# MSP-EXP430F5529LP.net
KiCad netlist of a schematic drawn in EAGLE
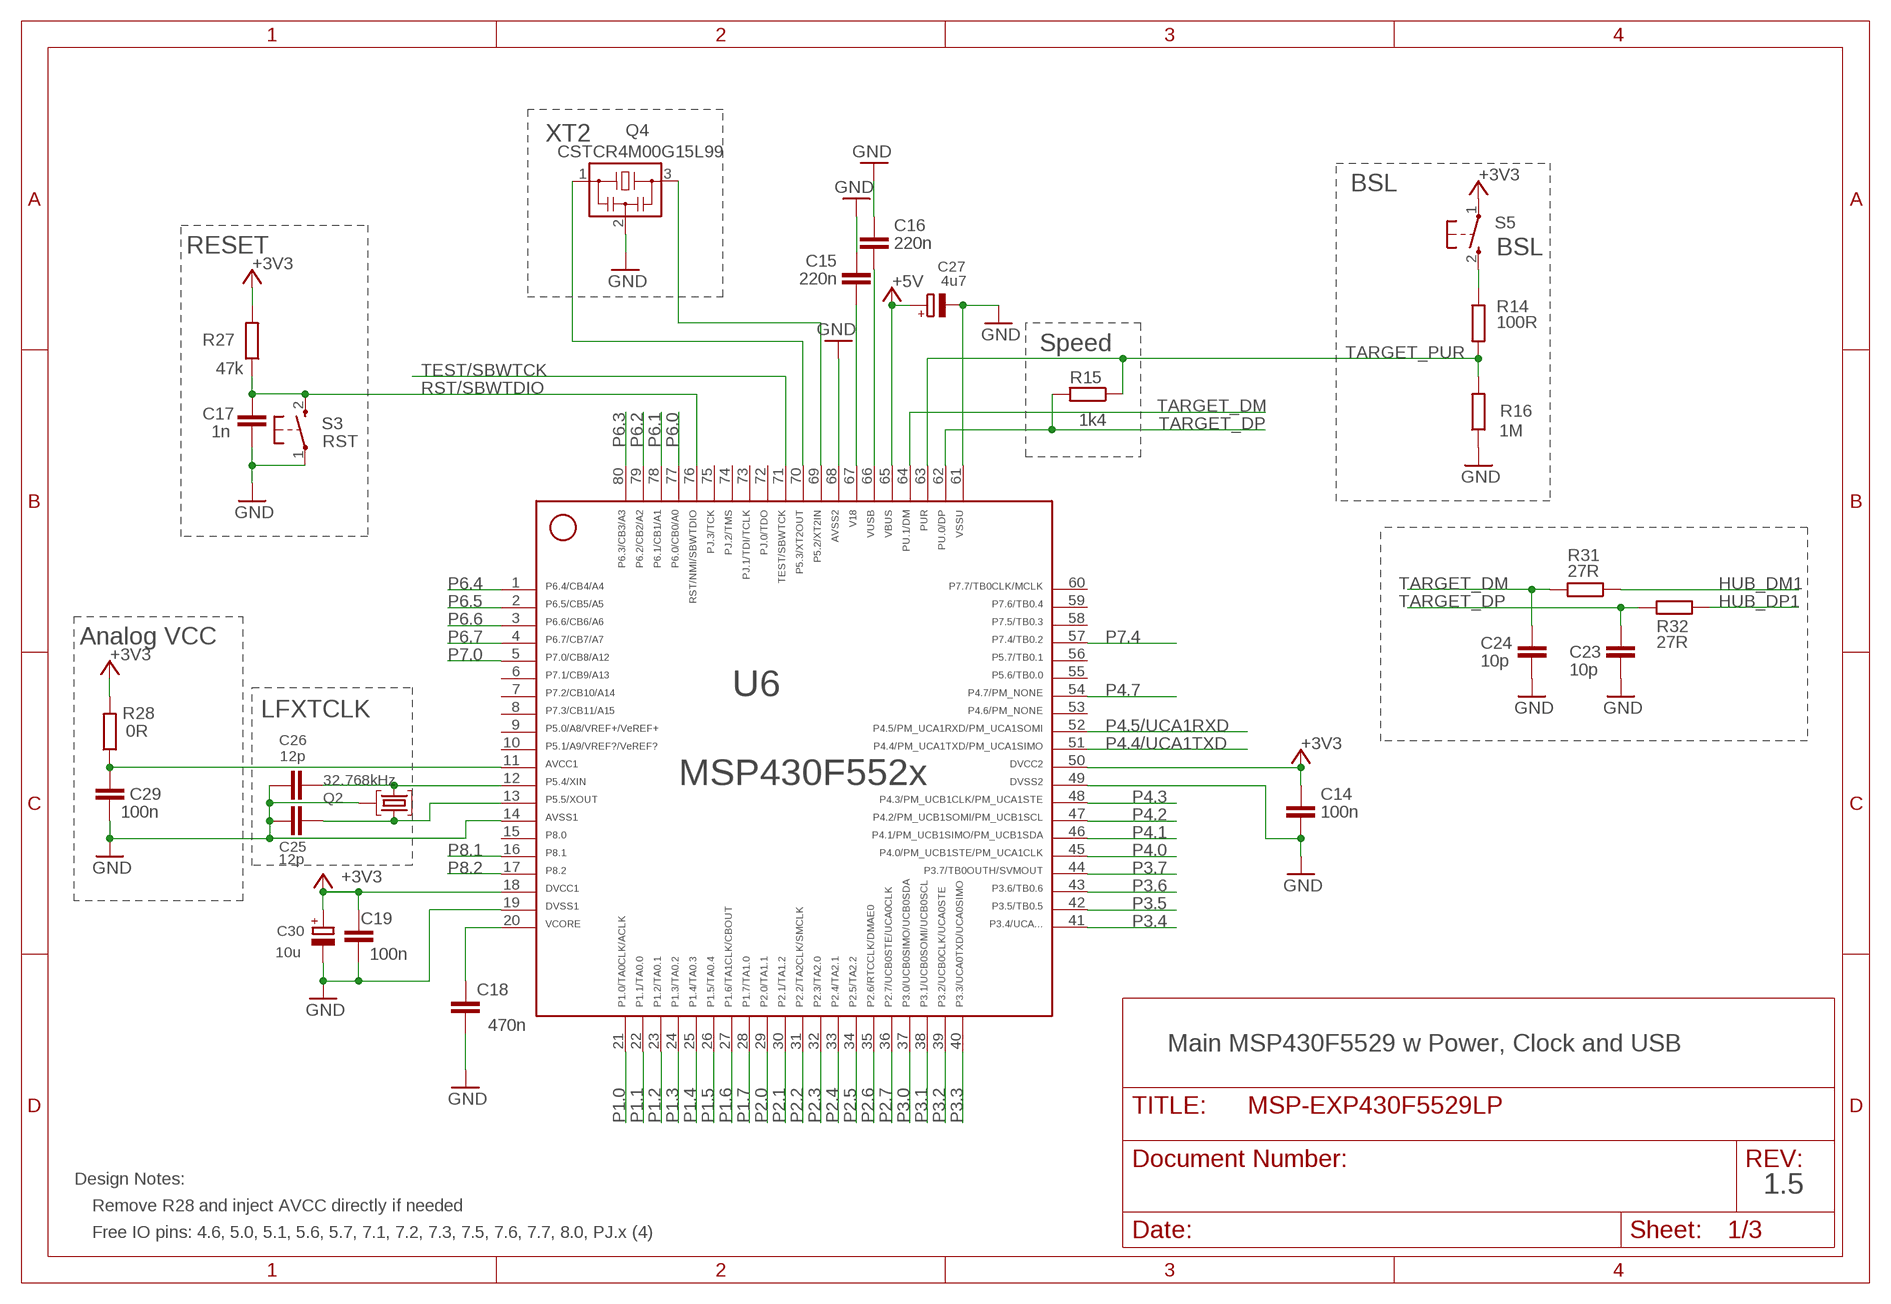
[diagram p0: schematic, sheet 1]
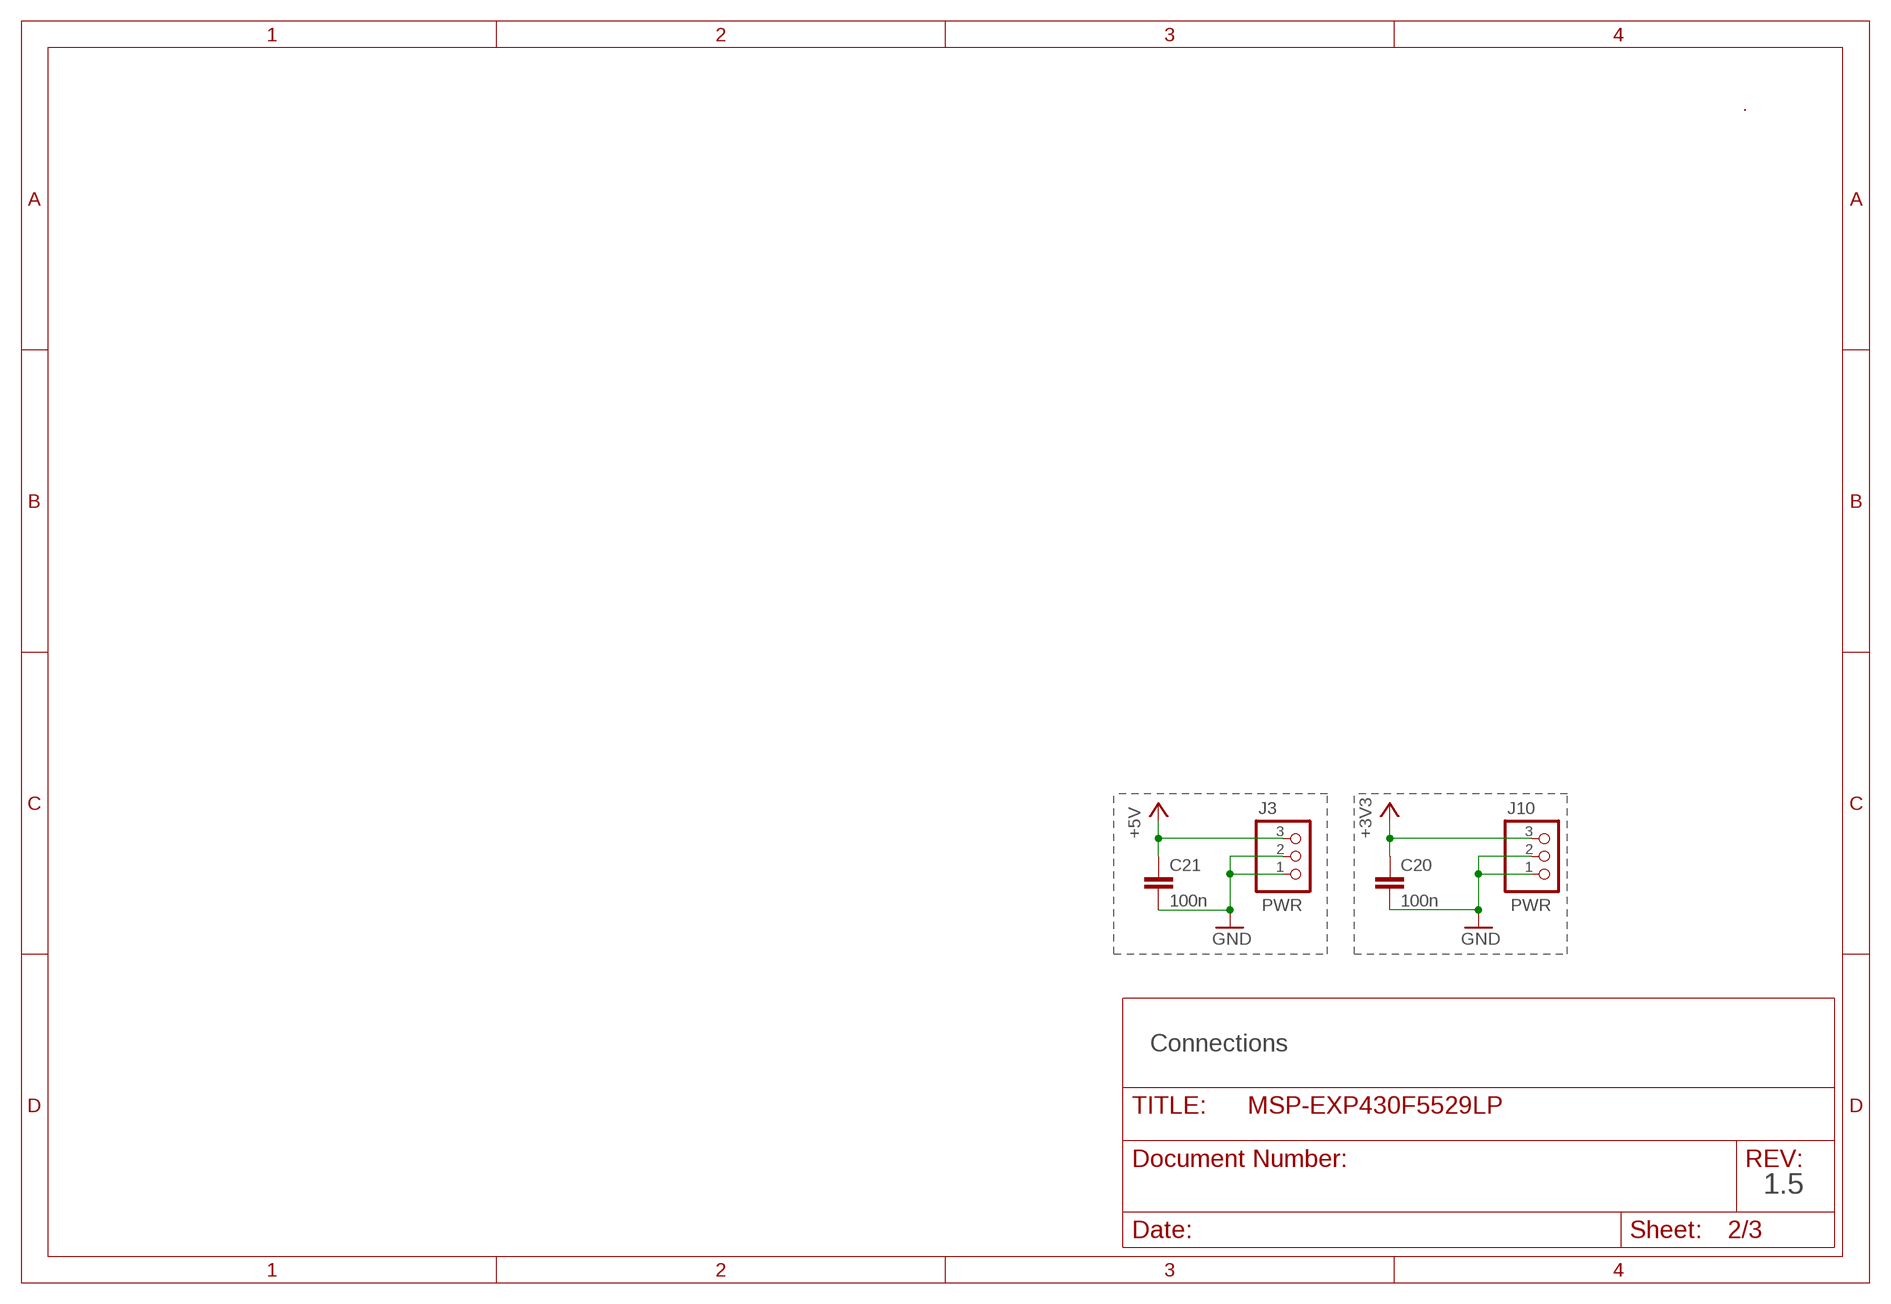
[diagram p1: schematic, sheet 2]
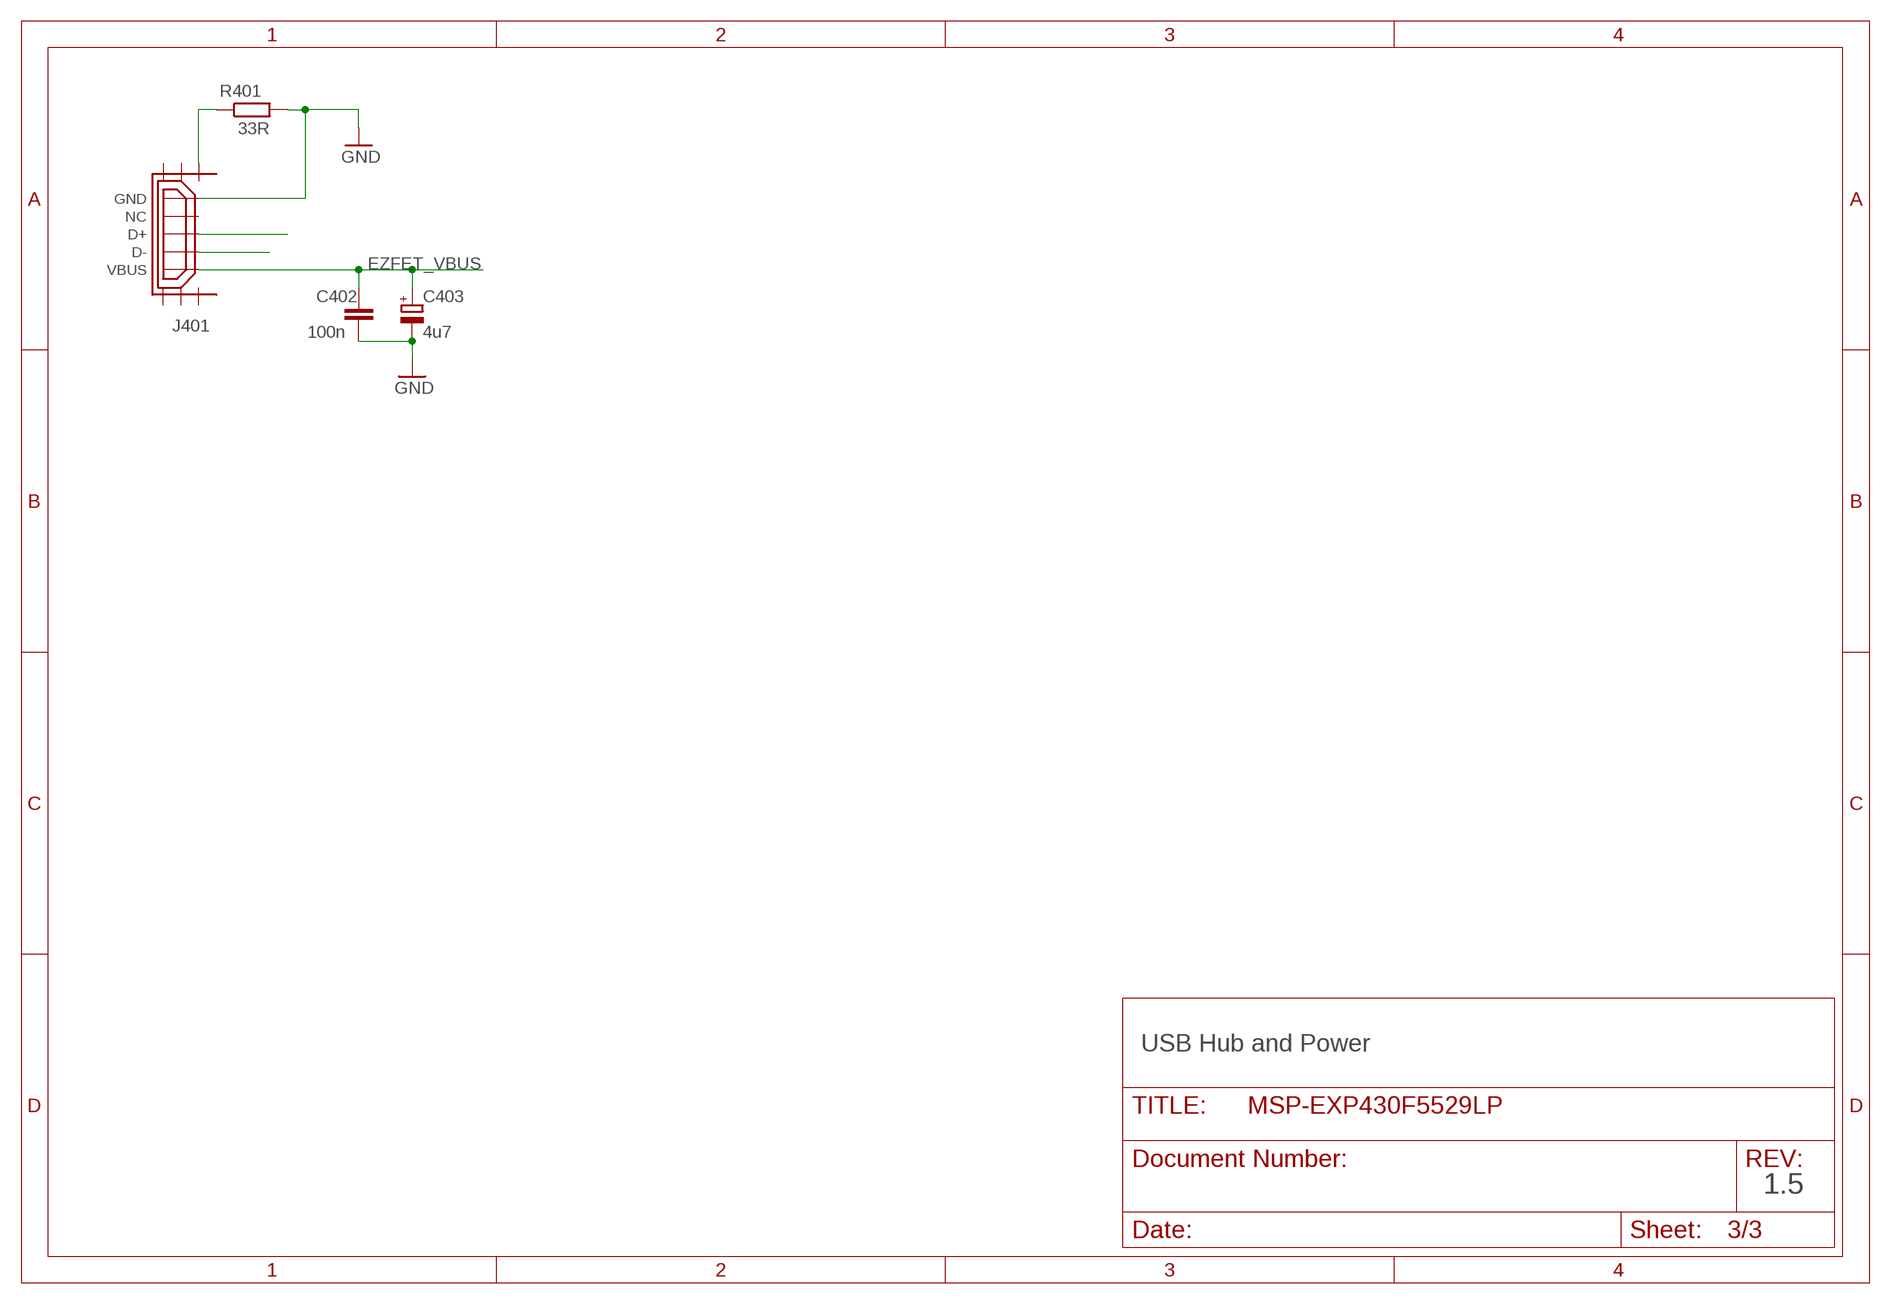
[diagram p2: schematic, sheet 3]

(export (version "E")
  (design (tool "Eeschema 10.0.6"))
  (components
    (comp (ref "C402")
      (value "100n")
      (footprint "eagle-import:C0402")
      (libsource (lib "eagle-import") (part "C-EUC0402"))
    )
    (comp (ref "C403")
      (value "4u7")
      (footprint "eagle-import:A_3216-18R")
      (libsource (lib "eagle-import") (part "CPOL-EUA/3216-18R"))
    )
    (comp (ref "J401")
      (value "USB_MICRO_FLIPPED")
      (footprint "eagle-import:HIROSE-ZX62R-B-5P")
      (libsource (lib "eagle-import") (part "USB_MICRO_FLIPPED"))
    )
    (comp (ref "R401")
      (value "33R")
      (footprint "eagle-import:R0402")
      (libsource (lib "eagle-import") (part "R-EU_R0402"))
    )
    (comp (ref "C20")
      (value "100n")
      (footprint "eagle-import:C0402")
      (libsource (lib "eagle-import") (part "C-EUC0402"))
    )
    (comp (ref "C21")
      (value "100n")
      (footprint "eagle-import:C0402")
      (libsource (lib "eagle-import") (part "C-EUC0402"))
    )
    (comp (ref "J3")
      (value "PWR")
      (footprint "eagle-import:1X03")
      (libsource (lib "eagle-import") (part "PINHD-1X3"))
    )
    (comp (ref "J10")
      (value "PWR")
      (footprint "eagle-import:1X03")
      (libsource (lib "eagle-import") (part "PINHD-1X3"))
    )
    (comp (ref "U$3")
      (value "5529_REAR_SILK_REV1_5_FINAL")
      (footprint "eagle-import:5529_REAR_SILK_REV1_5_FINAL")
      (libsource (lib "eagle-import") (part "5529_REAR_SILK_REV1_5_FINAL"))
    )
    (comp (ref "C14")
      (value "100n")
      (footprint "eagle-import:C0402")
      (libsource (lib "eagle-import") (part "C-EUC0402"))
    )
    (comp (ref "C15")
      (value "220n")
      (footprint "eagle-import:C0402")
      (libsource (lib "eagle-import") (part "C-EUC0402"))
    )
    (comp (ref "C16")
      (value "220n")
      (footprint "eagle-import:C0402")
      (libsource (lib "eagle-import") (part "C-EUC0402"))
    )
    (comp (ref "C17")
      (value "1n")
      (footprint "eagle-import:C0402")
      (libsource (lib "eagle-import") (part "C-EUC0402"))
    )
    (comp (ref "C18")
      (value "470n")
      (footprint "eagle-import:C0402")
      (libsource (lib "eagle-import") (part "C-EUC0402"))
    )
    (comp (ref "C19")
      (value "100n")
      (footprint "eagle-import:C0402")
      (libsource (lib "eagle-import") (part "C-EUC0402"))
    )
    (comp (ref "C23")
      (value "10p")
      (footprint "eagle-import:C0402")
      (libsource (lib "eagle-import") (part "C-EUC0402"))
    )
    (comp (ref "C24")
      (value "10p")
      (footprint "eagle-import:C0402")
      (libsource (lib "eagle-import") (part "C-EUC0402"))
    )
    (comp (ref "C25")
      (value "12p")
      (footprint "eagle-import:C0402")
      (libsource (lib "eagle-import") (part "C-EUC0402"))
    )
    (comp (ref "C26")
      (value "12p")
      (footprint "eagle-import:C0402")
      (libsource (lib "eagle-import") (part "C-EUC0402"))
    )
    (comp (ref "C27")
      (value "4u7")
      (footprint "eagle-import:A_3216-18R")
      (libsource (lib "eagle-import") (part "CPOL-EUA/3216-18R"))
    )
    (comp (ref "C29")
      (value "100n")
      (footprint "eagle-import:C0402")
      (libsource (lib "eagle-import") (part "C-EUC0402"))
    )
    (comp (ref "C30")
      (value "10u")
      (footprint "eagle-import:A_3216-18R")
      (libsource (lib "eagle-import") (part "CPOL-EUA/3216-18R"))
    )
    (comp (ref "Q2")
      (value "32.768kHz")
      (footprint "eagle-import:MS3V-T1R")
      (libsource (lib "eagle-import") (part "MS3V-T1R"))
    )
    (comp (ref "Q4")
      (value "CSTCR4M00G15L99")
      (footprint "eagle-import:MURATA-FILTER_CSTCR")
      (fields (field (name "MPN") "CSTCR6M00G53-R0"))
      (libsource (lib "eagle-import") (part "MURATA-FILTER_CSTCR6M00G53Z"))
    )
    (comp (ref "R14")
      (value "100R")
      (footprint "eagle-import:R0402")
      (libsource (lib "eagle-import") (part "R-EU_R0402"))
    )
    (comp (ref "R15")
      (value "1k4")
      (footprint "eagle-import:R0402")
      (libsource (lib "eagle-import") (part "R-EU_R0402"))
    )
    (comp (ref "R16")
      (value "1M")
      (footprint "eagle-import:R0402")
      (libsource (lib "eagle-import") (part "R-EU_R0402"))
    )
    (comp (ref "R27")
      (value "47k")
      (footprint "eagle-import:R0402")
      (libsource (lib "eagle-import") (part "R-EU_R0402"))
    )
    (comp (ref "R28")
      (value "0R")
      (footprint "eagle-import:R0402")
      (libsource (lib "eagle-import") (part "R-EU_R0402"))
    )
    (comp (ref "R31")
      (value "27R")
      (footprint "eagle-import:R0402")
      (libsource (lib "eagle-import") (part "R-EU_R0402"))
    )
    (comp (ref "R32")
      (value "27R")
      (footprint "eagle-import:R0402")
      (libsource (lib "eagle-import") (part "R-EU_R0402"))
    )
    (comp (ref "S3")
      (value "RST")
      (footprint "eagle-import:PBTH")
      (libsource (lib "eagle-import") (part "PB"))
    )
    (comp (ref "S5")
      (value "BSL")
      (footprint "eagle-import:PBTH")
      (libsource (lib "eagle-import") (part "PB"))
    )
    (comp (ref "U6")
      (value "MSP430F5529IPNR")
      (footprint "eagle-import:PN80")
      (libsource (lib "eagle-import") (part "F552X---PN80"))
    )
  )
  (nets
    (net (code "1") (name "+3V3") (class "Default")
      (node (ref "C14") (pin "1") (pinfunction "1_1") (pintype "passive"))
      (node (ref "C19") (pin "2") (pinfunction "2_2") (pintype "passive"))
      (node (ref "C20") (pin "1") (pinfunction "1_1") (pintype "passive"))
      (node (ref "C30") (pin "+") (pinfunction "+_+") (pintype "passive"))
      (node (ref "J10") (pin "3") (pinfunction "3_3") (pintype "passive"))
      (node (ref "R27") (pin "2") (pinfunction "2_2") (pintype "passive"))
      (node (ref "R28") (pin "2") (pinfunction "2_2") (pintype "passive"))
      (node (ref "S5") (pin "1") (pinfunction "P_1") (pintype "passive"))
      (node (ref "U6") (pin "18") (pinfunction "18_18") (pintype "power_in"))
      (node (ref "U6") (pin "50") (pinfunction "50_50") (pintype "power_in"))
    )
    (net (code "2") (name "+5V") (class "Default")
      (node (ref "C21") (pin "1") (pinfunction "1_1") (pintype "passive"))
      (node (ref "C27") (pin "+") (pinfunction "+_+") (pintype "passive"))
      (node (ref "J3") (pin "3") (pinfunction "3_3") (pintype "passive"))
      (node (ref "U6") (pin "65") (pinfunction "65_65") (pintype "power_in"))
    )
    (net (code "3") (name "EZFET_VBUS") (class "Default")
      (node (ref "C402") (pin "1") (pinfunction "1_1") (pintype "passive"))
      (node (ref "C403") (pin "+") (pinfunction "+_+") (pintype "passive"))
      (node (ref "J401") (pin "VBUS") (pinfunction "VBUS_VBUS") (pintype "input"))
    )
    (net (code "4") (name "GND") (class "Default")
      (node (ref "C14") (pin "2") (pinfunction "2_2") (pintype "passive"))
      (node (ref "C15") (pin "2") (pinfunction "2_2") (pintype "passive"))
      (node (ref "C16") (pin "2") (pinfunction "2_2") (pintype "passive"))
      (node (ref "C17") (pin "2") (pinfunction "2_2") (pintype "passive"))
      (node (ref "C18") (pin "1") (pinfunction "1_1") (pintype "passive"))
      (node (ref "C19") (pin "1") (pinfunction "1_1") (pintype "passive"))
      (node (ref "C20") (pin "2") (pinfunction "2_2") (pintype "passive"))
      (node (ref "C21") (pin "2") (pinfunction "2_2") (pintype "passive"))
      (node (ref "C23") (pin "2") (pinfunction "2_2") (pintype "passive"))
      (node (ref "C24") (pin "2") (pinfunction "2_2") (pintype "passive"))
      (node (ref "C25") (pin "1") (pinfunction "1_1") (pintype "passive"))
      (node (ref "C26") (pin "1") (pinfunction "1_1") (pintype "passive"))
      (node (ref "C27") (pin "-") (pinfunction "-_-") (pintype "passive"))
      (node (ref "C29") (pin "2") (pinfunction "2_2") (pintype "passive"))
      (node (ref "C30") (pin "-") (pinfunction "-_-") (pintype "passive"))
      (node (ref "C402") (pin "2") (pinfunction "2_2") (pintype "passive"))
      (node (ref "C403") (pin "-") (pinfunction "-_-") (pintype "passive"))
      (node (ref "J10") (pin "1") (pinfunction "1_1") (pintype "passive"))
      (node (ref "J10") (pin "2") (pinfunction "2_2") (pintype "passive"))
      (node (ref "J3") (pin "1") (pinfunction "1_1") (pintype "passive"))
      (node (ref "J3") (pin "2") (pinfunction "2_2") (pintype "passive"))
      (node (ref "J401") (pin "GND") (pinfunction "GND_GND") (pintype "input"))
      (node (ref "Q2") (pin "P3") (pinfunction "GND_P3") (pintype "power_in"))
      (node (ref "Q4") (pin "2") (pinfunction "2_2") (pintype "passive"))
      (node (ref "R16") (pin "1") (pinfunction "1_1") (pintype "passive"))
      (node (ref "R401") (pin "2") (pinfunction "2_2") (pintype "passive"))
      (node (ref "S3") (pin "1") (pinfunction "P_1") (pintype "passive"))
      (node (ref "U6") (pin "14") (pinfunction "14_14") (pintype "power_in"))
      (node (ref "U6") (pin "19") (pinfunction "19_19") (pintype "power_in"))
      (node (ref "U6") (pin "49") (pinfunction "49_49") (pintype "power_in"))
      (node (ref "U6") (pin "61") (pinfunction "61_61") (pintype "power_in"))
      (node (ref "U6") (pin "68") (pinfunction "68_68") (pintype "power_in"))
    )
    (net (code "5") (name "HUB_DM1") (class "Default")
      (node (ref "R31") (pin "1") (pinfunction "1_1") (pintype "passive"))
    )
    (net (code "6") (name "HUB_DP1") (class "Default")
      (node (ref "R32") (pin "1") (pinfunction "1_1") (pintype "passive"))
    )
    (net (code "7") (name "Net-(C15-Pad1)") (class "Default")
      (node (ref "C15") (pin "1") (pinfunction "1_1") (pintype "passive"))
      (node (ref "U6") (pin "67") (pinfunction "67_67") (pintype "power_in"))
    )
    (net (code "8") (name "Net-(C16-Pad1)") (class "Default")
      (node (ref "C16") (pin "1") (pinfunction "1_1") (pintype "passive"))
      (node (ref "U6") (pin "66") (pinfunction "66_66") (pintype "power_in"))
    )
    (net (code "9") (name "Net-(C18-Pad2)") (class "Default")
      (node (ref "C18") (pin "2") (pinfunction "2_2") (pintype "passive"))
      (node (ref "U6") (pin "20") (pinfunction "20_20") (pintype "power_in"))
    )
    (net (code "10") (name "Net-(C29-Pad1)") (class "Default")
      (node (ref "C29") (pin "1") (pinfunction "1_1") (pintype "passive"))
      (node (ref "R28") (pin "1") (pinfunction "1_1") (pintype "passive"))
      (node (ref "U6") (pin "11") (pinfunction "11_11") (pintype "power_in"))
    )
    (net (code "11") (name "Net-(J401-PadSHIELD1)") (class "Default")
      (node (ref "J401") (pin "SHIELD1") (pinfunction "SHIELD1_SHIELD1") (pintype "bidirectional"))
      (node (ref "R401") (pin "1") (pinfunction "1_1") (pintype "passive"))
    )
    (net (code "12") (name "Net-(Q2-1)") (class "Default")
      (node (ref "C25") (pin "2") (pinfunction "2_2") (pintype "passive"))
      (node (ref "Q2") (pin "P1") (pinfunction "1_P1") (pintype "bidirectional"))
      (node (ref "U6") (pin "13") (pinfunction "13_13") (pintype "bidirectional"))
    )
    (net (code "13") (name "Net-(Q2-2)") (class "Default")
      (node (ref "C26") (pin "2") (pinfunction "2_2") (pintype "passive"))
      (node (ref "Q2") (pin "P2") (pinfunction "2_P2") (pintype "bidirectional"))
      (node (ref "U6") (pin "12") (pinfunction "12_12") (pintype "bidirectional"))
    )
    (net (code "14") (name "Net-(Q4-Pad1)") (class "Default")
      (node (ref "Q4") (pin "1") (pinfunction "1_1") (pintype "passive"))
      (node (ref "U6") (pin "70") (pinfunction "70_70") (pintype "bidirectional"))
    )
    (net (code "15") (name "Net-(Q4-Pad3)") (class "Default")
      (node (ref "Q4") (pin "3") (pinfunction "3_3") (pintype "passive"))
      (node (ref "U6") (pin "69") (pinfunction "69_69") (pintype "bidirectional"))
    )
    (net (code "16") (name "Net-(S5-S)") (class "Default")
      (node (ref "R14") (pin "1") (pinfunction "1_1") (pintype "passive"))
      (node (ref "S5") (pin "2") (pinfunction "S_2") (pintype "passive"))
    )
    (net (code "17") (name "P1.0") (class "Default")
      (node (ref "U6") (pin "21") (pinfunction "21_21") (pintype "bidirectional"))
    )
    (net (code "18") (name "P1.1") (class "Default")
      (node (ref "U6") (pin "22") (pinfunction "22_22") (pintype "bidirectional"))
    )
    (net (code "19") (name "P1.2") (class "Default")
      (node (ref "U6") (pin "23") (pinfunction "23_23") (pintype "bidirectional"))
    )
    (net (code "20") (name "P1.3") (class "Default")
      (node (ref "U6") (pin "24") (pinfunction "24_24") (pintype "bidirectional"))
    )
    (net (code "21") (name "P1.4") (class "Default")
      (node (ref "U6") (pin "25") (pinfunction "25_25") (pintype "bidirectional"))
    )
    (net (code "22") (name "P1.5") (class "Default")
      (node (ref "U6") (pin "26") (pinfunction "26_26") (pintype "bidirectional"))
    )
    (net (code "23") (name "P1.6") (class "Default")
      (node (ref "U6") (pin "27") (pinfunction "27_27") (pintype "bidirectional"))
    )
    (net (code "24") (name "P1.7") (class "Default")
      (node (ref "U6") (pin "28") (pinfunction "28_28") (pintype "bidirectional"))
    )
    (net (code "25") (name "P2.0") (class "Default")
      (node (ref "U6") (pin "29") (pinfunction "29_29") (pintype "bidirectional"))
    )
    (net (code "26") (name "P2.1") (class "Default")
      (node (ref "U6") (pin "30") (pinfunction "30_30") (pintype "bidirectional"))
    )
    (net (code "27") (name "P2.2") (class "Default")
      (node (ref "U6") (pin "31") (pinfunction "31_31") (pintype "bidirectional"))
    )
    (net (code "28") (name "P2.3") (class "Default")
      (node (ref "U6") (pin "32") (pinfunction "32_32") (pintype "bidirectional"))
    )
    (net (code "29") (name "P2.4") (class "Default")
      (node (ref "U6") (pin "33") (pinfunction "33_33") (pintype "bidirectional"))
    )
    (net (code "30") (name "P2.5") (class "Default")
      (node (ref "U6") (pin "34") (pinfunction "34_34") (pintype "bidirectional"))
    )
    (net (code "31") (name "P2.6") (class "Default")
      (node (ref "U6") (pin "35") (pinfunction "35_35") (pintype "bidirectional"))
    )
    (net (code "32") (name "P2.7") (class "Default")
      (node (ref "U6") (pin "36") (pinfunction "36_36") (pintype "bidirectional"))
    )
    (net (code "33") (name "P3.0") (class "Default")
      (node (ref "U6") (pin "37") (pinfunction "37_37") (pintype "bidirectional"))
    )
    (net (code "34") (name "P3.1") (class "Default")
      (node (ref "U6") (pin "38") (pinfunction "38_38") (pintype "bidirectional"))
    )
    (net (code "35") (name "P3.2") (class "Default")
      (node (ref "U6") (pin "39") (pinfunction "39_39") (pintype "bidirectional"))
    )
    (net (code "36") (name "P3.3") (class "Default")
      (node (ref "U6") (pin "40") (pinfunction "40_40") (pintype "bidirectional"))
    )
    (net (code "37") (name "P3.4") (class "Default")
      (node (ref "U6") (pin "41") (pinfunction "41_41") (pintype "bidirectional"))
    )
    (net (code "38") (name "P3.5") (class "Default")
      (node (ref "U6") (pin "42") (pinfunction "42_42") (pintype "bidirectional"))
    )
    (net (code "39") (name "P3.6") (class "Default")
      (node (ref "U6") (pin "43") (pinfunction "43_43") (pintype "bidirectional"))
    )
    (net (code "40") (name "P3.7") (class "Default")
      (node (ref "U6") (pin "44") (pinfunction "44_44") (pintype "bidirectional"))
    )
    (net (code "41") (name "P4.0") (class "Default")
      (node (ref "U6") (pin "45") (pinfunction "45_45") (pintype "bidirectional"))
    )
    (net (code "42") (name "P4.1") (class "Default")
      (node (ref "U6") (pin "46") (pinfunction "46_46") (pintype "bidirectional"))
    )
    (net (code "43") (name "P4.2") (class "Default")
      (node (ref "U6") (pin "47") (pinfunction "47_47") (pintype "bidirectional"))
    )
    (net (code "44") (name "P4.3") (class "Default")
      (node (ref "U6") (pin "48") (pinfunction "48_48") (pintype "bidirectional"))
    )
    (net (code "45") (name "P4.4{slash}UCA1TXD") (class "Default")
      (node (ref "U6") (pin "51") (pinfunction "51_51") (pintype "bidirectional"))
    )
    (net (code "46") (name "P4.5{slash}UCA1RXD") (class "Default")
      (node (ref "U6") (pin "52") (pinfunction "52_52") (pintype "bidirectional"))
    )
    (net (code "47") (name "P4.7") (class "Default")
      (node (ref "U6") (pin "54") (pinfunction "54_54") (pintype "bidirectional"))
    )
    (net (code "48") (name "P6.0") (class "Default")
      (node (ref "U6") (pin "77") (pinfunction "77_77") (pintype "bidirectional"))
    )
    (net (code "49") (name "P6.1") (class "Default")
      (node (ref "U6") (pin "78") (pinfunction "78_78") (pintype "bidirectional"))
    )
    (net (code "50") (name "P6.2") (class "Default")
      (node (ref "U6") (pin "79") (pinfunction "79_79") (pintype "bidirectional"))
    )
    (net (code "51") (name "P6.3") (class "Default")
      (node (ref "U6") (pin "80") (pinfunction "80_80") (pintype "bidirectional"))
    )
    (net (code "52") (name "P6.4") (class "Default")
      (node (ref "U6") (pin "1") (pinfunction "1_1") (pintype "bidirectional"))
    )
    (net (code "53") (name "P6.5") (class "Default")
      (node (ref "U6") (pin "2") (pinfunction "2_2") (pintype "bidirectional"))
    )
    (net (code "54") (name "P6.6") (class "Default")
      (node (ref "U6") (pin "3") (pinfunction "3_3") (pintype "bidirectional"))
    )
    (net (code "55") (name "P6.7") (class "Default")
      (node (ref "U6") (pin "4") (pinfunction "4_4") (pintype "bidirectional"))
    )
    (net (code "56") (name "P7.0") (class "Default")
      (node (ref "U6") (pin "5") (pinfunction "5_5") (pintype "bidirectional"))
    )
    (net (code "57") (name "P7.4") (class "Default")
      (node (ref "U6") (pin "57") (pinfunction "57_57") (pintype "bidirectional"))
    )
    (net (code "58") (name "P8.1") (class "Default")
      (node (ref "U6") (pin "16") (pinfunction "16_16") (pintype "bidirectional"))
    )
    (net (code "59") (name "P8.2") (class "Default")
      (node (ref "U6") (pin "17") (pinfunction "17_17") (pintype "bidirectional"))
    )
    (net (code "60") (name "RST{slash}SBWTDIO") (class "Default")
      (node (ref "C17") (pin "1") (pinfunction "1_1") (pintype "passive"))
      (node (ref "R27") (pin "1") (pinfunction "1_1") (pintype "passive"))
      (node (ref "S3") (pin "2") (pinfunction "S_2") (pintype "passive"))
      (node (ref "U6") (pin "76") (pinfunction "76_76") (pintype "bidirectional"))
    )
    (net (code "61") (name "TARGET_DM") (class "Default")
      (node (ref "C24") (pin "1") (pinfunction "1_1") (pintype "passive"))
      (node (ref "R31") (pin "2") (pinfunction "2_2") (pintype "passive"))
      (node (ref "U6") (pin "64") (pinfunction "64_64") (pintype "bidirectional"))
    )
    (net (code "62") (name "TARGET_DP") (class "Default")
      (node (ref "C23") (pin "1") (pinfunction "1_1") (pintype "passive"))
      (node (ref "R15") (pin "2") (pinfunction "2_2") (pintype "passive"))
      (node (ref "R32") (pin "2") (pinfunction "2_2") (pintype "passive"))
      (node (ref "U6") (pin "62") (pinfunction "62_62") (pintype "bidirectional"))
    )
    (net (code "63") (name "TARGET_PUR") (class "Default")
      (node (ref "R14") (pin "2") (pinfunction "2_2") (pintype "passive"))
      (node (ref "R15") (pin "1") (pinfunction "1_1") (pintype "passive"))
      (node (ref "R16") (pin "2") (pinfunction "2_2") (pintype "passive"))
      (node (ref "U6") (pin "63") (pinfunction "63_63") (pintype "bidirectional"))
    )
    (net (code "64") (name "TEST{slash}SBWTCK") (class "Default")
      (node (ref "U6") (pin "71") (pinfunction "71_71") (pintype "input"))
    )
    (net (code "65") (name "unconnected-(J401-PadD+)") (class "Default")
      (node (ref "J401") (pin "D+") (pinfunction "D+_D+") (pintype "input"))
    )
    (net (code "66") (name "unconnected-(J401-PadD-)") (class "Default")
      (node (ref "J401") (pin "D-") (pinfunction "D-_D-") (pintype "input"))
    )
    (net (code "67") (name "unconnected-(J401-PadNC)") (class "Default")
      (node (ref "J401") (pin "NC") (pinfunction "NC_NC") (pintype "input"))
    )
    (net (code "68") (name "unconnected-(J401-PadSHIELD2)") (class "Default")
      (node (ref "J401") (pin "SHIELD2") (pinfunction "SHIELD2_SHIELD2") (pintype "bidirectional"))
    )
    (net (code "69") (name "unconnected-(J401-PadSHIELD3)") (class "Default")
      (node (ref "J401") (pin "SHIELD3") (pinfunction "SHIELD3_SHIELD3") (pintype "bidirectional"))
    )
    (net (code "70") (name "unconnected-(J401-PadSHIELD4)") (class "Default")
      (node (ref "J401") (pin "SHIELD4") (pinfunction "SHIELD4_SHIELD4") (pintype "bidirectional"))
    )
    (net (code "71") (name "unconnected-(J401-PadSHIELD5)") (class "Default")
      (node (ref "J401") (pin "SHIELD5") (pinfunction "SHIELD5_SHIELD5") (pintype "bidirectional"))
    )
    (net (code "72") (name "unconnected-(J401-PadSHIELD6)") (class "Default")
      (node (ref "J401") (pin "SHIELD6") (pinfunction "SHIELD6_SHIELD6") (pintype "bidirectional"))
    )
    (net (code "73") (name "unconnected-(U6-Pad6)") (class "Default")
      (node (ref "U6") (pin "6") (pinfunction "6_6") (pintype "bidirectional"))
    )
    (net (code "74") (name "unconnected-(U6-Pad7)") (class "Default")
      (node (ref "U6") (pin "7") (pinfunction "7_7") (pintype "bidirectional"))
    )
    (net (code "75") (name "unconnected-(U6-Pad8)") (class "Default")
      (node (ref "U6") (pin "8") (pinfunction "8_8") (pintype "bidirectional"))
    )
    (net (code "76") (name "unconnected-(U6-Pad9)") (class "Default")
      (node (ref "U6") (pin "9") (pinfunction "9_9") (pintype "bidirectional"))
    )
    (net (code "77") (name "unconnected-(U6-Pad10)") (class "Default")
      (node (ref "U6") (pin "10") (pinfunction "10_10") (pintype "bidirectional"))
    )
    (net (code "78") (name "unconnected-(U6-Pad15)") (class "Default")
      (node (ref "U6") (pin "15") (pinfunction "15_15") (pintype "bidirectional"))
    )
    (net (code "79") (name "unconnected-(U6-Pad53)") (class "Default")
      (node (ref "U6") (pin "53") (pinfunction "53_53") (pintype "bidirectional"))
    )
    (net (code "80") (name "unconnected-(U6-Pad55)") (class "Default")
      (node (ref "U6") (pin "55") (pinfunction "55_55") (pintype "bidirectional"))
    )
    (net (code "81") (name "unconnected-(U6-Pad56)") (class "Default")
      (node (ref "U6") (pin "56") (pinfunction "56_56") (pintype "bidirectional"))
    )
    (net (code "82") (name "unconnected-(U6-Pad58)") (class "Default")
      (node (ref "U6") (pin "58") (pinfunction "58_58") (pintype "bidirectional"))
    )
    (net (code "83") (name "unconnected-(U6-Pad59)") (class "Default")
      (node (ref "U6") (pin "59") (pinfunction "59_59") (pintype "bidirectional"))
    )
    (net (code "84") (name "unconnected-(U6-Pad60)") (class "Default")
      (node (ref "U6") (pin "60") (pinfunction "60_60") (pintype "bidirectional"))
    )
    (net (code "85") (name "unconnected-(U6-Pad72)") (class "Default")
      (node (ref "U6") (pin "72") (pinfunction "72_72") (pintype "bidirectional"))
    )
    (net (code "86") (name "unconnected-(U6-Pad73)") (class "Default")
      (node (ref "U6") (pin "73") (pinfunction "73_73") (pintype "bidirectional"))
    )
    (net (code "87") (name "unconnected-(U6-Pad74)") (class "Default")
      (node (ref "U6") (pin "74") (pinfunction "74_74") (pintype "bidirectional"))
    )
    (net (code "88") (name "unconnected-(U6-Pad75)") (class "Default")
      (node (ref "U6") (pin "75") (pinfunction "75_75") (pintype "bidirectional"))
    )
  )
)
